# LPC1768_0.net
KiCad netlist of a schematic drawn in Altium Designer
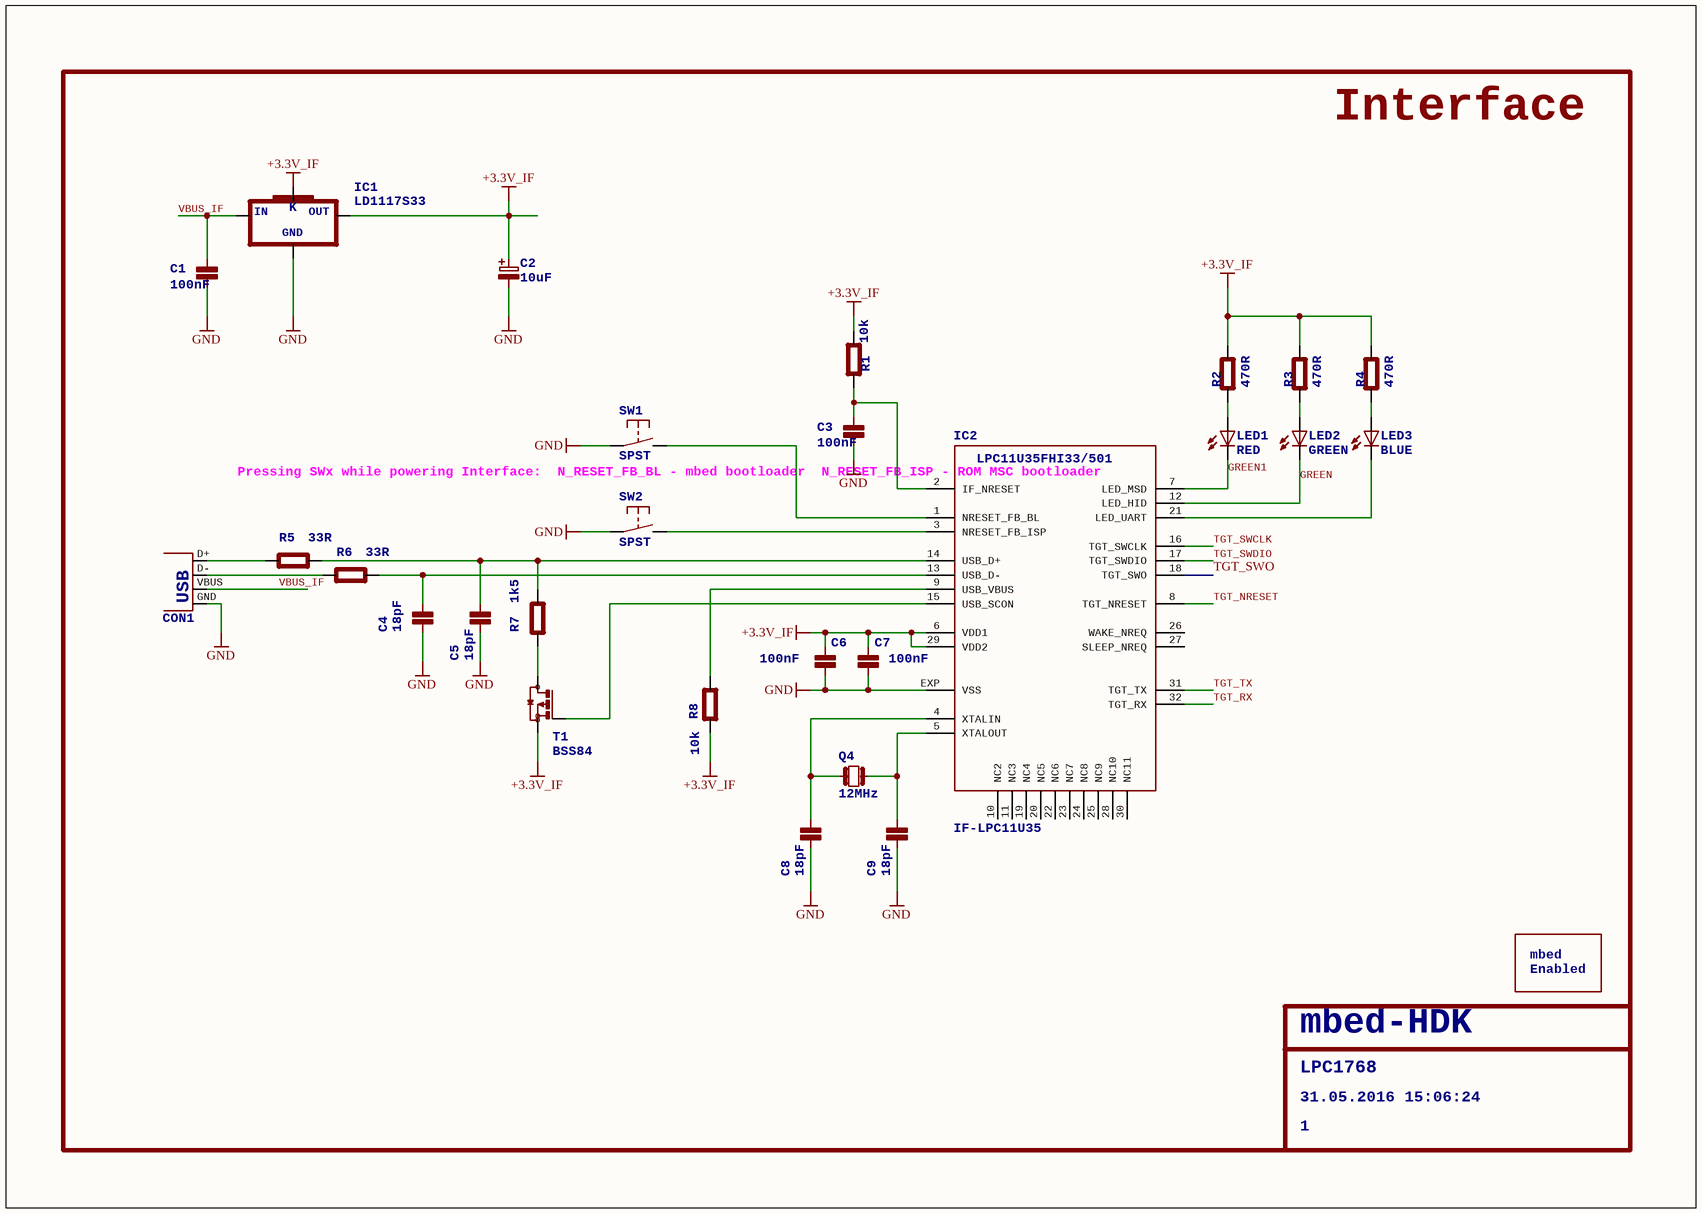
[diagram p0: LPC1768_0.SchDoc]

(export (version "E")
  (design (tool "Eeschema 10.0.6"))
  (components
    (comp (ref "C1") (value "100nF") (footprint "0603") (libsource (lib "mbed-HDK") (part "C0603")))
    (comp (ref "C2") (value "10uF") (footprint "CASE-B") (libsource (lib "mbed-HDK") (part "C-POLB")))
    (comp (ref "C3") (value "100nF") (footprint "0603") (libsource (lib "mbed-HDK") (part "C0603")))
    (comp (ref "C4") (value "18pF") (footprint "0603") (libsource (lib "") (part "C0603_1")))
    (comp (ref "C5") (value "18pF") (footprint "0603") (libsource (lib "") (part "C0603_1")))
    (comp (ref "C6") (value "100nF") (footprint "0603") (libsource (lib "mbed-HDK") (part "C0603")))
    (comp (ref "C7") (value "100nF") (footprint "0603") (libsource (lib "mbed-HDK") (part "C0603")))
    (comp (ref "C8") (value "18pF") (footprint "0603") (libsource (lib "") (part "C0603_1")))
    (comp (ref "C9") (value "18pF") (footprint "0603") (libsource (lib "") (part "C0603_1")))
    (comp (ref "CON1")
      (value "USB-MB-S")
      (footprint "USB-MB-S")
      (description "USB Connectors")
      (fields (field (name "USB") "USB"))
      (libsource (lib "mbed-HDK") (part "USB-MB-S"))
    )
    (comp (ref "IC1")
      (value "LD1117S33")
      (footprint "SOT223")
      (description "VOLTAGE REGULATOR SMD 3,3V")
      (fields
        (field (name "GND") "GND")
        (field (name "IN") "IN")
        (field (name "OUT") "OUT")
        (field (name "K") "K")
      )
      (libsource (lib "mbed-HDK") (part "LD1117S33"))
    )
    (comp (ref "IC2")
      (value "IF-LPC11U35")
      (footprint "HVQFN33")
      (fields (field (name "LPC11U35FHI33/501") "LPC11U35FHI33/501"))
      (libsource (lib "mbed-HDK") (part "IF-LPC11U35"))
    )
    (comp (ref "LED1") (value "RED") (footprint "CHIPLED_0603") (libsource (lib "mbed-HDK") (part "LED0603")))
    (comp (ref "LED2")
      (value "GREEN")
      (footprint "CHIPLED_0603")
      (libsource (lib "mbed-HDK") (part "LED0603"))
    )
    (comp (ref "LED3")
      (value "BLUE")
      (footprint "CHIPLED_0603")
      (libsource (lib "mbed-HDK") (part "LED0603"))
    )
    (comp (ref "Q4") (value "12MHz") (footprint "HC49UP") (libsource (lib "mbed-HDK") (part "Q_HC49UP")))
    (comp (ref "R1") (value "10k") (footprint "0603") (libsource (lib "mbed-HDK") (part "R0603")))
    (comp (ref "R2") (value "470R") (footprint "0603") (libsource (lib "mbed-HDK") (part "R0603")))
    (comp (ref "R3") (value "470R") (footprint "0603") (libsource (lib "mbed-HDK") (part "R0603")))
    (comp (ref "R4") (value "470R") (footprint "0603") (libsource (lib "mbed-HDK") (part "R0603")))
    (comp (ref "R5") (value "33R") (footprint "0603") (libsource (lib "mbed-HDK") (part "R0603")))
    (comp (ref "R6") (value "33R") (footprint "0603") (libsource (lib "mbed-HDK") (part "R0603")))
    (comp (ref "R7") (value "1k5") (footprint "0603") (libsource (lib "mbed-HDK") (part "R0603")))
    (comp (ref "R8") (value "10k") (footprint "0603") (libsource (lib "mbed-HDK") (part "R0603")))
    (comp (ref "SS1")
      (value "MBED-ENABLED-LOGOMEDIUM")
      (footprint "MBED-ENABLED-LOGO-500X500-MIL")
      (fields (field (name "MBED") "mbed") (field (name "ENABLED") "Enabled"))
      (libsource (lib "mbed-HDK") (part "MBED-ENABLED-LOGOMEDIUM"))
    )
    (comp (ref "SW1") (value "SPST") (footprint "DTSM-32S-B") (libsource (lib "mbed-HDK") (part "SPST")))
    (comp (ref "SW2") (value "SPST") (footprint "DTSM-32S-B") (libsource (lib "mbed-HDK") (part "SPST")))
    (comp (ref "T1")
      (value "BSS84")
      (footprint "SOT23")
      (description "P-CHANNEL MOS FET")
      (libsource (lib "mbed-HDK") (part "BSS84"))
    )
  )
  (nets
    (net (code "1") (name "+3.3V_IF") (class "Default")
      (node (ref "C2") (pin "1") (pinfunction "1_1") (pintype "passive"))
      (node (ref "C6") (pin "1") (pinfunction "P$1_1") (pintype "passive"))
      (node (ref "C7") (pin "1") (pinfunction "P$1_1") (pintype "passive"))
      (node (ref "IC1") (pin "2") (pinfunction "OUT_2") (pintype "passive"))
      (node (ref "IC1") (pin "4") (pinfunction "K_4") (pintype "passive"))
      (node (ref "IC2") (pin "29") (pinfunction "VDD2_29") (pintype "passive"))
      (node (ref "IC2") (pin "6") (pinfunction "VDD1_6") (pintype "passive"))
      (node (ref "R1") (pin "2") (pinfunction "P$2_2") (pintype "passive"))
      (node (ref "R2") (pin "1") (pinfunction "P$1_1") (pintype "passive"))
      (node (ref "R3") (pin "1") (pinfunction "P$1_1") (pintype "passive"))
      (node (ref "R4") (pin "1") (pinfunction "P$1_1") (pintype "passive"))
      (node (ref "R8") (pin "2") (pinfunction "P$2_2") (pintype "passive"))
      (node (ref "T1") (pin "2") (pinfunction "S_2") (pintype "passive"))
    )
    (net (code "2") (name "/GREEN") (class "Default")
      (node (ref "IC2") (pin "12") (pinfunction "LED_HID_12") (pintype "passive"))
      (node (ref "LED2") (pin "C") (pinfunction "C_C") (pintype "passive"))
    )
    (net (code "3") (name "/GREEN1") (class "Default")
      (node (ref "IC2") (pin "7") (pinfunction "LED_MSD_7") (pintype "passive"))
      (node (ref "LED1") (pin "C") (pinfunction "C_C") (pintype "passive"))
    )
    (net (code "4") (name "/TGT_NRESET") (class "Default")
      (node (ref "IC2") (pin "8") (pinfunction "TGT_NRESET_8") (pintype "passive"))
    )
    (net (code "5") (name "/TGT_RX") (class "Default")
      (node (ref "IC2") (pin "32") (pinfunction "TGT_RX_32") (pintype "passive"))
    )
    (net (code "6") (name "/TGT_SWCLK") (class "Default")
      (node (ref "IC2") (pin "16") (pinfunction "TGT_SWCLK_16") (pintype "passive"))
    )
    (net (code "7") (name "/TGT_SWDIO") (class "Default")
      (node (ref "IC2") (pin "17") (pinfunction "TGT_SWDIO_17") (pintype "passive"))
    )
    (net (code "8") (name "/TGT_SWO") (class "Default")
      (node (ref "IC2") (pin "18") (pinfunction "TGT_SWO_18") (pintype "passive"))
    )
    (net (code "9") (name "/TGT_TX") (class "Default")
      (node (ref "IC2") (pin "31") (pinfunction "TGT_TX_31") (pintype "passive"))
    )
    (net (code "10") (name "/VBUS_IF") (class "Default")
      (node (ref "C1") (pin "1") (pinfunction "P$1_1") (pintype "passive"))
      (node (ref "CON1") (pin "VBUS") (pinfunction "VBUS_VBUS") (pintype "passive"))
      (node (ref "IC1") (pin "3") (pinfunction "IN_3") (pintype "passive"))
    )
    (net (code "11") (name "GND") (class "Default")
      (node (ref "C1") (pin "2") (pinfunction "P$2_2") (pintype "passive"))
      (node (ref "C2") (pin "2") (pinfunction "2_2") (pintype "passive"))
      (node (ref "C3") (pin "2") (pinfunction "P$2_2") (pintype "passive"))
      (node (ref "C4") (pin "2") (pinfunction "P$2_2") (pintype "passive"))
      (node (ref "C5") (pin "2") (pinfunction "P$2_2") (pintype "passive"))
      (node (ref "C6") (pin "2") (pinfunction "P$2_2") (pintype "passive"))
      (node (ref "C7") (pin "2") (pinfunction "P$2_2") (pintype "passive"))
      (node (ref "C8") (pin "2") (pinfunction "P$2_2") (pintype "passive"))
      (node (ref "C9") (pin "2") (pinfunction "P$2_2") (pintype "passive"))
      (node (ref "CON1") (pin "GND") (pinfunction "GND_GND") (pintype "passive"))
      (node (ref "IC1") (pin "1") (pinfunction "GND_1") (pintype "passive"))
      (node (ref "IC2") (pin "EXP") (pinfunction "VSS_EXP") (pintype "passive"))
      (node (ref "SW1") (pin "P$1") (pinfunction "P_P$1") (pintype "passive"))
      (node (ref "SW2") (pin "P$1") (pinfunction "P_P$1") (pintype "passive"))
    )
    (net (code "12") (name "Net-(C3-P$1)") (class "Default")
      (node (ref "C3") (pin "1") (pinfunction "P$1_1") (pintype "passive"))
      (node (ref "IC2") (pin "2") (pinfunction "IF_NRESET_2") (pintype "passive"))
      (node (ref "R1") (pin "1") (pinfunction "P$1_1") (pintype "passive"))
    )
    (net (code "13") (name "Net-(C4-P$1)") (class "Default")
      (node (ref "C4") (pin "1") (pinfunction "P$1_1") (pintype "passive"))
      (node (ref "IC2") (pin "13") (pinfunction "USB_D-_13") (pintype "passive"))
      (node (ref "R6") (pin "2") (pinfunction "P$2_2") (pintype "passive"))
    )
    (net (code "14") (name "Net-(C5-P$1)") (class "Default")
      (node (ref "C5") (pin "1") (pinfunction "P$1_1") (pintype "passive"))
      (node (ref "IC2") (pin "14") (pinfunction "USB_D+_14") (pintype "passive"))
      (node (ref "R5") (pin "2") (pinfunction "P$2_2") (pintype "passive"))
      (node (ref "R7") (pin "2") (pinfunction "P$2_2") (pintype "passive"))
    )
    (net (code "15") (name "Net-(C8-P$1)") (class "Default")
      (node (ref "C8") (pin "1") (pinfunction "P$1_1") (pintype "passive"))
      (node (ref "IC2") (pin "4") (pinfunction "XTALIN_4") (pintype "passive"))
      (node (ref "Q4") (pin "1") (pinfunction "1_1") (pintype "passive"))
    )
    (net (code "16") (name "Net-(C9-P$1)") (class "Default")
      (node (ref "C9") (pin "1") (pinfunction "P$1_1") (pintype "passive"))
      (node (ref "IC2") (pin "5") (pinfunction "XTALOUT_5") (pintype "passive"))
      (node (ref "Q4") (pin "2") (pinfunction "2_2") (pintype "passive"))
    )
    (net (code "17") (name "Net-(IC2-LED_UART)") (class "Default")
      (node (ref "IC2") (pin "21") (pinfunction "LED_UART_21") (pintype "passive"))
      (node (ref "LED3") (pin "C") (pinfunction "C_C") (pintype "passive"))
    )
    (net (code "18") (name "Net-(IC2-NRESET_FB_BL)") (class "Default")
      (node (ref "IC2") (pin "1") (pinfunction "NRESET_FB_BL_1") (pintype "passive"))
      (node (ref "SW1") (pin "P$2") (pinfunction "S_P$2") (pintype "passive"))
    )
    (net (code "19") (name "Net-(IC2-NRESET_FB_ISP)") (class "Default")
      (node (ref "IC2") (pin "3") (pinfunction "NRESET_FB_ISP_3") (pintype "passive"))
      (node (ref "SW2") (pin "P$2") (pinfunction "S_P$2") (pintype "passive"))
    )
    (net (code "20") (name "Net-(IC2-USB_SCON)") (class "Default")
      (node (ref "IC2") (pin "15") (pinfunction "USB_SCON_15") (pintype "passive"))
      (node (ref "T1") (pin "1") (pinfunction "G_1") (pintype "passive"))
    )
    (net (code "21") (name "Net-(IC2-USB_VBUS)") (class "Default")
      (node (ref "IC2") (pin "9") (pinfunction "USB_VBUS_9") (pintype "passive"))
      (node (ref "R8") (pin "1") (pinfunction "P$1_1") (pintype "passive"))
    )
    (net (code "22") (name "Net-(R2-P$2)") (class "Default")
      (node (ref "LED1") (pin "A") (pinfunction "A_A") (pintype "passive"))
      (node (ref "R2") (pin "2") (pinfunction "P$2_2") (pintype "passive"))
    )
    (net (code "23") (name "Net-(R3-P$2)") (class "Default")
      (node (ref "LED2") (pin "A") (pinfunction "A_A") (pintype "passive"))
      (node (ref "R3") (pin "2") (pinfunction "P$2_2") (pintype "passive"))
    )
    (net (code "24") (name "Net-(R4-P$2)") (class "Default")
      (node (ref "LED3") (pin "A") (pinfunction "A_A") (pintype "passive"))
      (node (ref "R4") (pin "2") (pinfunction "P$2_2") (pintype "passive"))
    )
    (net (code "25") (name "Net-(R5-P$1)") (class "Default")
      (node (ref "CON1") (pin "D+") (pinfunction "D+_D+") (pintype "passive"))
      (node (ref "R5") (pin "1") (pinfunction "P$1_1") (pintype "passive"))
    )
    (net (code "26") (name "Net-(R6-P$1)") (class "Default")
      (node (ref "CON1") (pin "D-") (pinfunction "D-_D-") (pintype "passive"))
      (node (ref "R6") (pin "1") (pinfunction "P$1_1") (pintype "passive"))
    )
    (net (code "27") (name "Net-(R7-P$1)") (class "Default")
      (node (ref "R7") (pin "1") (pinfunction "P$1_1") (pintype "passive"))
      (node (ref "T1") (pin "3") (pinfunction "D_3") (pintype "passive"))
    )
    (net (code "28") (name "unconnected-(IC2-NC2-Pad10)") (class "Default")
      (node (ref "IC2") (pin "10") (pinfunction "NC2_10") (pintype "passive"))
    )
    (net (code "29") (name "unconnected-(IC2-NC3-Pad11)") (class "Default")
      (node (ref "IC2") (pin "11") (pinfunction "NC3_11") (pintype "passive"))
    )
    (net (code "30") (name "unconnected-(IC2-NC4-Pad19)") (class "Default")
      (node (ref "IC2") (pin "19") (pinfunction "NC4_19") (pintype "passive"))
    )
    (net (code "31") (name "unconnected-(IC2-NC5-Pad20)") (class "Default")
      (node (ref "IC2") (pin "20") (pinfunction "NC5_20") (pintype "passive"))
    )
    (net (code "32") (name "unconnected-(IC2-NC6-Pad22)") (class "Default")
      (node (ref "IC2") (pin "22") (pinfunction "NC6_22") (pintype "passive"))
    )
    (net (code "33") (name "unconnected-(IC2-NC7-Pad23)") (class "Default")
      (node (ref "IC2") (pin "23") (pinfunction "NC7_23") (pintype "passive"))
    )
    (net (code "34") (name "unconnected-(IC2-NC8-Pad24)") (class "Default")
      (node (ref "IC2") (pin "24") (pinfunction "NC8_24") (pintype "passive"))
    )
    (net (code "35") (name "unconnected-(IC2-NC9-Pad25)") (class "Default")
      (node (ref "IC2") (pin "25") (pinfunction "NC9_25") (pintype "passive"))
    )
    (net (code "36") (name "unconnected-(IC2-NC10-Pad28)") (class "Default")
      (node (ref "IC2") (pin "28") (pinfunction "NC10_28") (pintype "passive"))
    )
    (net (code "37") (name "unconnected-(IC2-NC11-Pad30)") (class "Default")
      (node (ref "IC2") (pin "30") (pinfunction "NC11_30") (pintype "passive"))
    )
    (net (code "38") (name "unconnected-(IC2-SLEEP_NREQ-Pad27)") (class "Default")
      (node (ref "IC2") (pin "27") (pinfunction "SLEEP_NREQ_27") (pintype "passive"))
    )
    (net (code "39") (name "unconnected-(IC2-WAKE_NREQ-Pad26)") (class "Default")
      (node (ref "IC2") (pin "26") (pinfunction "WAKE_NREQ_26") (pintype "passive"))
    )
  )
)
